# Project_Kondrashova_motor_driver.net
KiCad netlist of a schematic drawn in Altium Designer
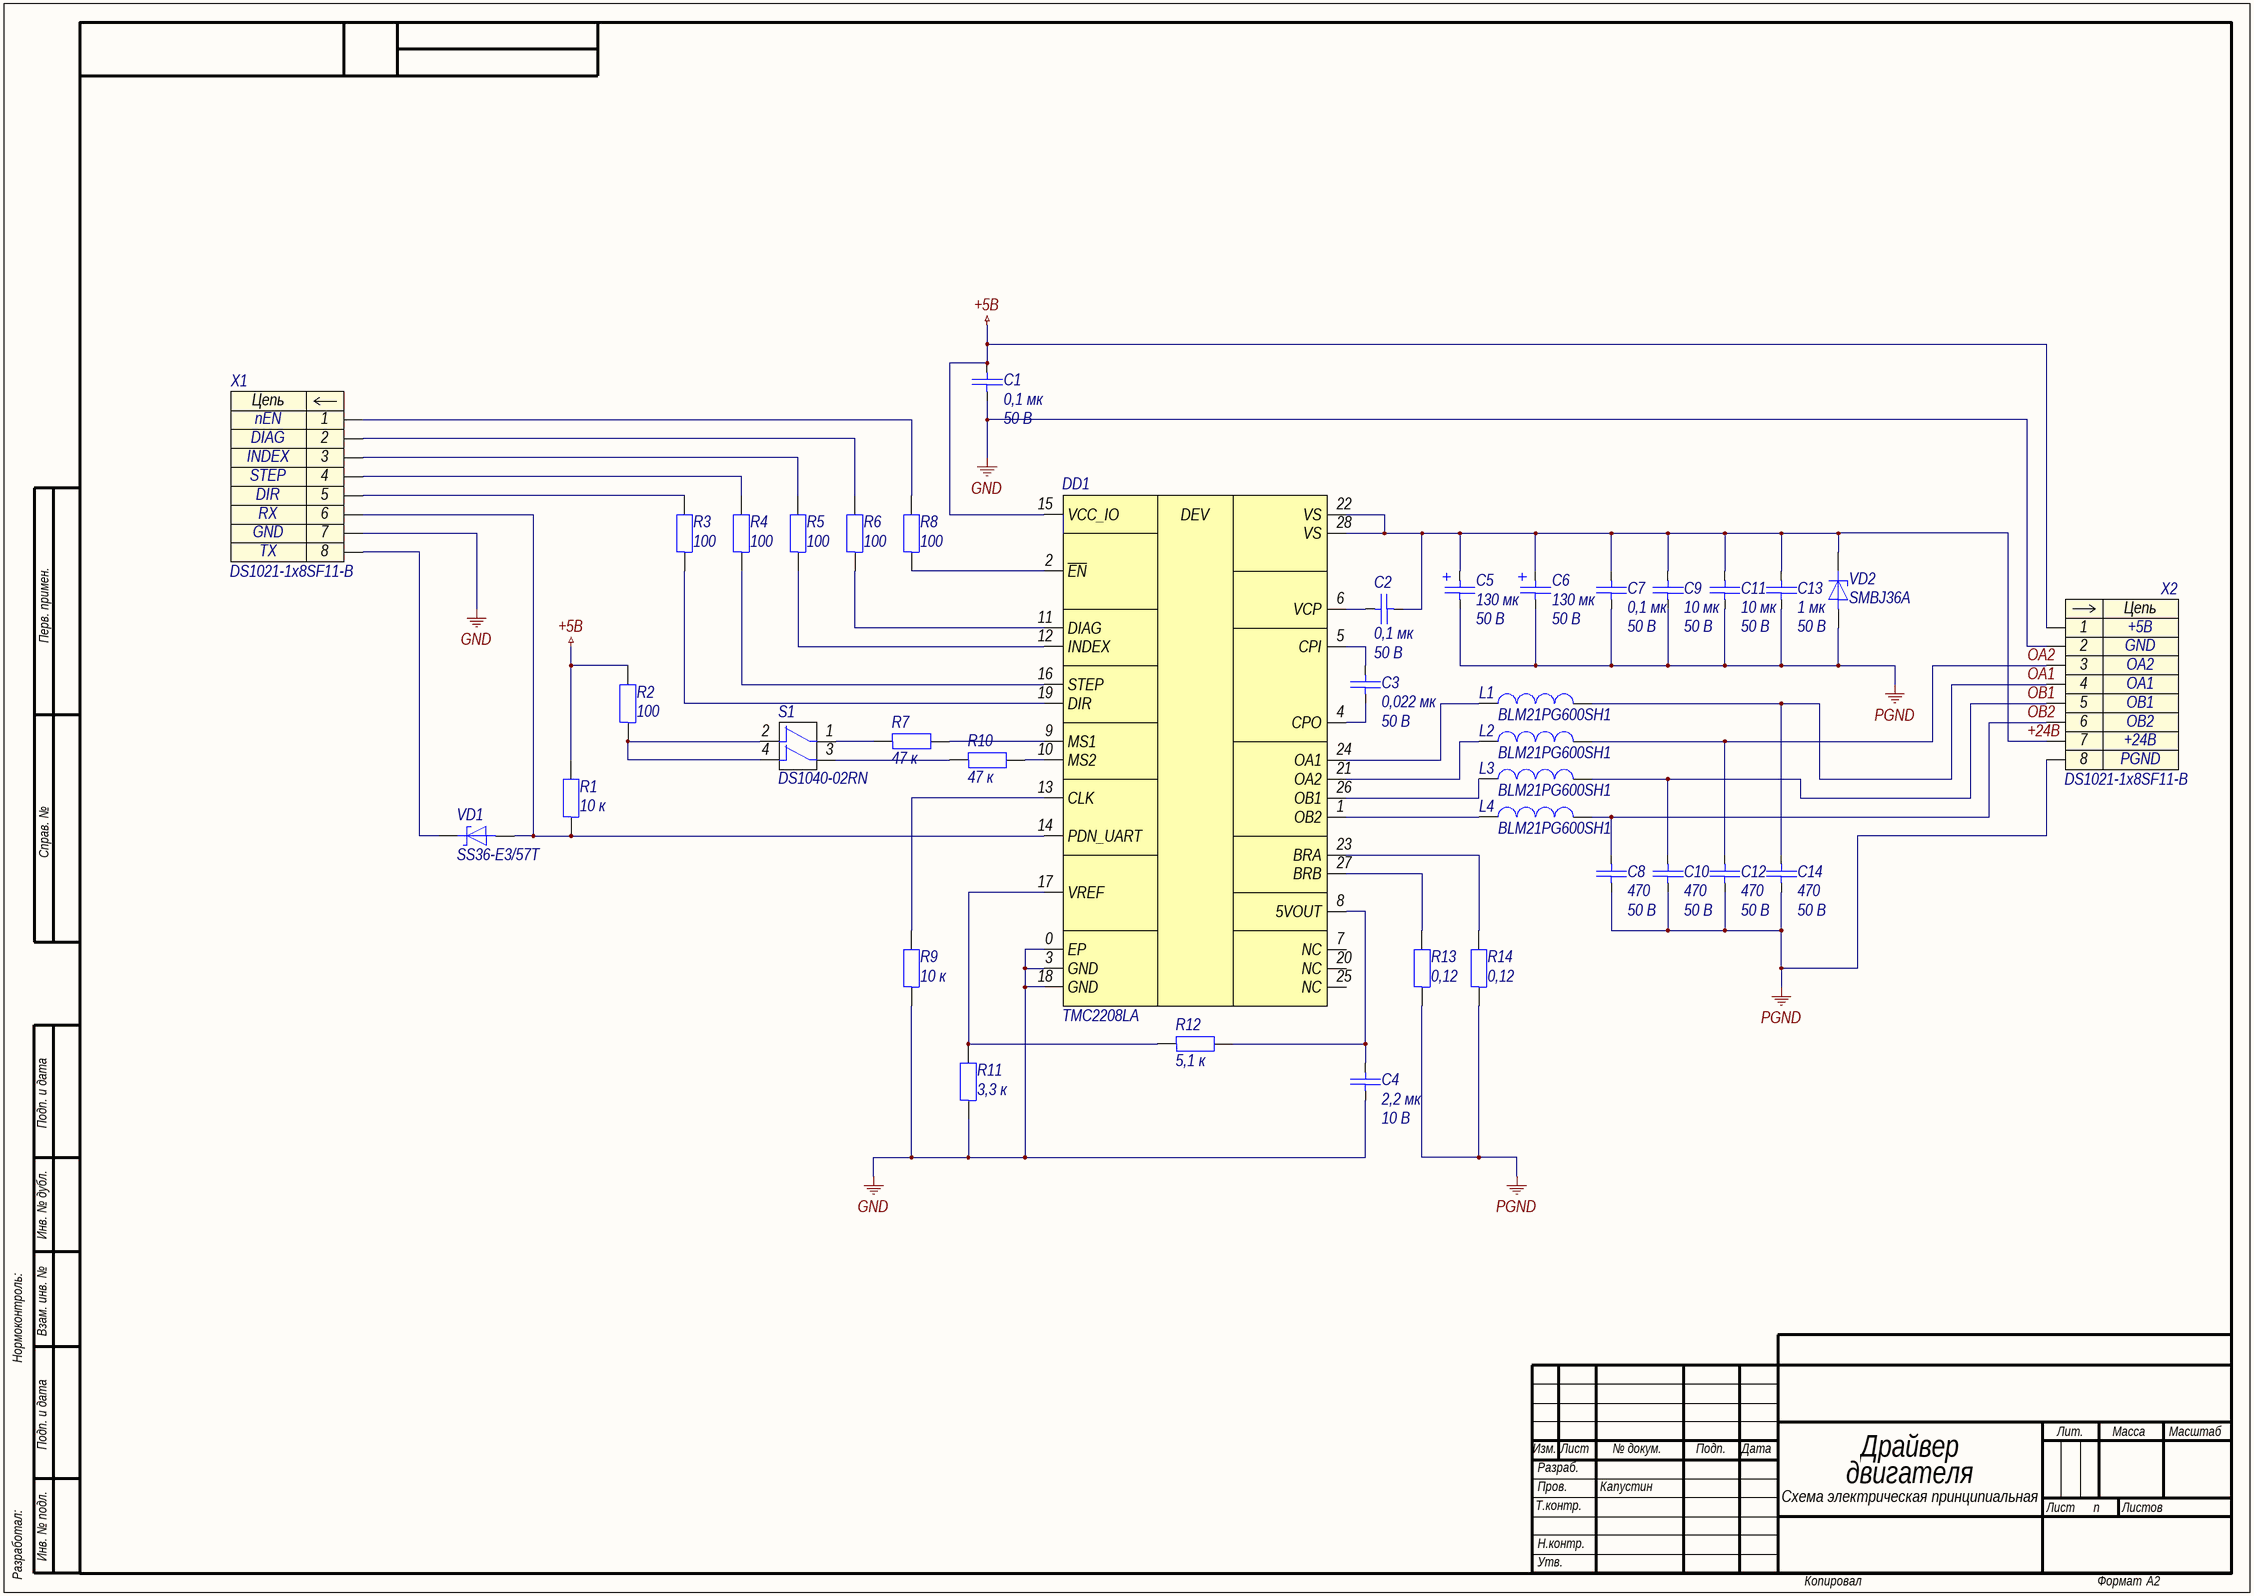
[diagram p0: Project_Kondrashova_motor_driver.SchDoc]

(export (version "E")
  (design (tool "Eeschema 10.0.6"))
  (components
    (comp (ref "C1")
      (value "0,1 мк")
      (footprint "C0603")
      (description "=Описание")
      (fields (field (name "НАПРЯЖЕНИЕ") "50 В"))
      (libsource (lib "Database_Students") (part "CAPACITOR-NONPOLAR"))
    )
    (comp (ref "C2")
      (value "0,1 мк")
      (footprint "C0603")
      (description "=Описание")
      (fields (field (name "НАПРЯЖЕНИЕ") "50 В"))
      (libsource (lib "Database_Students") (part "CAPACITOR-NONPOLAR"))
    )
    (comp (ref "C3")
      (value "0,022 мк")
      (footprint "C0603")
      (description "=Описание")
      (fields (field (name "НАПРЯЖЕНИЕ") "50 В"))
      (libsource (lib "Database_Students") (part "CAPACITOR-NONPOLAR"))
    )
    (comp (ref "C4")
      (value "2,2 мк")
      (footprint "C0603")
      (description "=Описание")
      (fields (field (name "НАПРЯЖЕНИЕ") "10 В"))
      (libsource (lib "Database_Students") (part "CAPACITOR-NONPOLAR"))
    )
    (comp (ref "C5")
      (value "130 мк")
      (footprint "C7343-43")
      (description "=Описание")
      (fields (field (name "НАПРЯЖЕНИЕ") "50 В"))
      (libsource (lib "Database_Students") (part "CAPACITOR-POLAR"))
    )
    (comp (ref "C6")
      (value "130 мк")
      (footprint "C7343-43")
      (description "=Описание")
      (fields (field (name "НАПРЯЖЕНИЕ") "50 В"))
      (libsource (lib "Database_Students") (part "CAPACITOR-POLAR"))
    )
    (comp (ref "C7")
      (value "0,1 мк")
      (footprint "C0603")
      (description "=Описание")
      (fields (field (name "НАПРЯЖЕНИЕ") "50 В"))
      (libsource (lib "Database_Students") (part "CAPACITOR-NONPOLAR"))
    )
    (comp (ref "C8")
      (value "470")
      (footprint "C0603")
      (description "=Описание")
      (fields (field (name "НАПРЯЖЕНИЕ") "50 В"))
      (libsource (lib "Database_Students") (part "CAPACITOR-NONPOLAR"))
    )
    (comp (ref "C9")
      (value "10 мк")
      (footprint "C2220")
      (description "=Описание")
      (fields (field (name "НАПРЯЖЕНИЕ") "50 В"))
      (libsource (lib "Database_Students") (part "CAPACITOR-NONPOLAR"))
    )
    (comp (ref "C10")
      (value "470")
      (footprint "C0603")
      (description "=Описание")
      (fields (field (name "НАПРЯЖЕНИЕ") "50 В"))
      (libsource (lib "Database_Students") (part "CAPACITOR-NONPOLAR"))
    )
    (comp (ref "C11")
      (value "10 мк")
      (footprint "C2220")
      (description "=Описание")
      (fields (field (name "НАПРЯЖЕНИЕ") "50 В"))
      (libsource (lib "Database_Students") (part "CAPACITOR-NONPOLAR"))
    )
    (comp (ref "C12")
      (value "470")
      (footprint "C0603")
      (description "=Описание")
      (fields (field (name "НАПРЯЖЕНИЕ") "50 В"))
      (libsource (lib "Database_Students") (part "CAPACITOR-NONPOLAR"))
    )
    (comp (ref "C13")
      (value "1 мк")
      (footprint "C1210")
      (description "=Описание")
      (fields (field (name "НАПРЯЖЕНИЕ") "50 В"))
      (libsource (lib "Database_Students") (part "CAPACITOR-NONPOLAR"))
    )
    (comp (ref "C14")
      (value "470")
      (footprint "C0603")
      (description "=Описание")
      (fields (field (name "НАПРЯЖЕНИЕ") "50 В"))
      (libsource (lib "Database_Students") (part "CAPACITOR-NONPOLAR"))
    )
    (comp (ref "DD1")
      (value "TMC2208LA")
      (footprint "QFN-28-P50-500X500X90-L55X25-T310X310")
      (description "=Описание")
      (libsource (lib "Database_Students") (part "TMC2208-LA"))
    )
    (comp (ref "L1")
      (value "BLM21PG600SH1")
      (footprint "MI-2-0805")
      (description "=Описание")
      (libsource (lib "Database_Students") (part "FERRITE-BEAD"))
    )
    (comp (ref "L2")
      (value "BLM21PG600SH1")
      (footprint "MI-2-0805")
      (description "=Описание")
      (libsource (lib "Database_Students") (part "FERRITE-BEAD"))
    )
    (comp (ref "L3")
      (value "BLM21PG600SH1")
      (footprint "MI-2-0805")
      (description "=Описание")
      (libsource (lib "Database_Students") (part "FERRITE-BEAD"))
    )
    (comp (ref "L4")
      (value "BLM21PG600SH1")
      (footprint "MI-2-0805")
      (description "=Описание")
      (libsource (lib "Database_Students") (part "FERRITE-BEAD"))
    )
    (comp (ref "R1")
      (value "10 к")
      (footprint "R0603")
      (description "=Описание")
      (libsource (lib "Database_Students") (part "RESISTOR-COMMON"))
    )
    (comp (ref "R2")
      (value "100")
      (footprint "R0603")
      (description "=Описание")
      (libsource (lib "Database_Students") (part "RESISTOR-COMMON"))
    )
    (comp (ref "R3")
      (value "100")
      (footprint "R0603")
      (description "=Описание")
      (libsource (lib "Database_Students") (part "RESISTOR-COMMON"))
    )
    (comp (ref "R4")
      (value "100")
      (footprint "R0603")
      (description "=Описание")
      (libsource (lib "Database_Students") (part "RESISTOR-COMMON"))
    )
    (comp (ref "R5")
      (value "100")
      (footprint "R0603")
      (description "=Описание")
      (libsource (lib "Database_Students") (part "RESISTOR-COMMON"))
    )
    (comp (ref "R6")
      (value "100")
      (footprint "R0603")
      (description "=Описание")
      (libsource (lib "Database_Students") (part "RESISTOR-COMMON"))
    )
    (comp (ref "R7")
      (value "47 к")
      (footprint "R0603")
      (description "=Описание")
      (libsource (lib "Database_Students") (part "RESISTOR-COMMON"))
    )
    (comp (ref "R8")
      (value "100")
      (footprint "R0603")
      (description "=Описание")
      (libsource (lib "Database_Students") (part "RESISTOR-COMMON"))
    )
    (comp (ref "R9")
      (value "10 к")
      (footprint "R0603")
      (description "=Описание")
      (libsource (lib "Database_Students") (part "RESISTOR-COMMON"))
    )
    (comp (ref "R10")
      (value "47 к")
      (footprint "R0603")
      (description "=Описание")
      (libsource (lib "Database_Students") (part "RESISTOR-COMMON"))
    )
    (comp (ref "R11")
      (value "3,3 к")
      (footprint "R0603")
      (description "=Описание")
      (libsource (lib "Database_Students") (part "RESISTOR-COMMON"))
    )
    (comp (ref "R12")
      (value "5,1 к")
      (footprint "R0603")
      (description "=Описание")
      (libsource (lib "Database_Students") (part "RESISTOR-COMMON"))
    )
    (comp (ref "R13")
      (value "0,12")
      (footprint "R0603")
      (description "=Описание")
      (libsource (lib "Database_Students") (part "RESISTOR-COMMON"))
    )
    (comp (ref "R14")
      (value "0,12")
      (footprint "R0603")
      (description "=Описание")
      (libsource (lib "Database_Students") (part "RESISTOR-COMMON"))
    )
    (comp (ref "S1")
      (value "DS1040-02RN")
      (footprint "DS1040-02RN")
      (description "=Описание")
      (libsource (lib "Database_Students") (part "SWITCH-4C"))
    )
    (comp (ref "VD1")
      (value "SS36-E3/57T")
      (footprint "DO-214AB-790X590X262")
      (description "=Описание")
      (libsource (lib "Database_Students") (part "DIODE-SCHOTTKY"))
    )
    (comp (ref "VD2")
      (value "SMBJ36A")
      (footprint "SMBJ36A")
      (description "=Описание")
      (libsource (lib "Database_Students") (part "DIODE-ZENER"))
    )
    (comp (ref "X1")
      (value "DS1021-1x8SF11-B")
      (footprint "DS1021-1X8SF11-B")
      (description "=Описание")
      (libsource (lib "Database_Students") (part "HEADER-8-PLG"))
    )
    (comp (ref "X2")
      (value "DS1021-1x8SF11-B")
      (footprint "DS1021-1X8SF11-B")
      (description "=Описание")
      (libsource (lib "") (part "HEADER-8-PLG_1"))
    )
  )
  (nets
    (net (code "1") (name "+5В") (class "Default")
      (node (ref "C1") (pin "1") (pinfunction "1_1") (pintype "passive"))
      (node (ref "DD1") (pin "15") (pinfunction "VCC_IO_15") (pintype "passive"))
      (node (ref "R1") (pin "2") (pinfunction "2_2") (pintype "passive"))
      (node (ref "R2") (pin "2") (pinfunction "2_2") (pintype "passive"))
      (node (ref "X2") (pin "1") (pinfunction "1_1") (pintype "passive"))
    )
    (net (code "2") (name "/+24В") (class "Default")
      (node (ref "C11") (pin "1") (pinfunction "1_1") (pintype "passive"))
      (node (ref "C13") (pin "1") (pinfunction "1_1") (pintype "passive"))
      (node (ref "C2") (pin "2") (pinfunction "2_2") (pintype "passive"))
      (node (ref "C5") (pin "1") (pinfunction "1_1") (pintype "passive"))
      (node (ref "C6") (pin "1") (pinfunction "1_1") (pintype "passive"))
      (node (ref "C7") (pin "1") (pinfunction "1_1") (pintype "passive"))
      (node (ref "C9") (pin "1") (pinfunction "1_1") (pintype "passive"))
      (node (ref "DD1") (pin "22") (pinfunction "VS_22") (pintype "passive"))
      (node (ref "DD1") (pin "28") (pinfunction "VS_28") (pintype "passive"))
      (node (ref "VD2") (pin "1") (pinfunction "1_1") (pintype "passive"))
      (node (ref "X2") (pin "7") (pinfunction "7_7") (pintype "passive"))
    )
    (net (code "3") (name "/OA1") (class "Default")
      (node (ref "C14") (pin "1") (pinfunction "1_1") (pintype "passive"))
      (node (ref "L1") (pin "2") (pinfunction "2_2") (pintype "passive"))
      (node (ref "X2") (pin "4") (pinfunction "4_4") (pintype "passive"))
    )
    (net (code "4") (name "/OA2") (class "Default")
      (node (ref "C12") (pin "1") (pinfunction "1_1") (pintype "passive"))
      (node (ref "L2") (pin "2") (pinfunction "2_2") (pintype "passive"))
      (node (ref "X2") (pin "3") (pinfunction "3_3") (pintype "passive"))
    )
    (net (code "5") (name "/OB1") (class "Default")
      (node (ref "C10") (pin "1") (pinfunction "1_1") (pintype "passive"))
      (node (ref "L3") (pin "2") (pinfunction "2_2") (pintype "passive"))
      (node (ref "X2") (pin "5") (pinfunction "5_5") (pintype "passive"))
    )
    (net (code "6") (name "/OB2") (class "Default")
      (node (ref "C8") (pin "1") (pinfunction "1_1") (pintype "passive"))
      (node (ref "L4") (pin "2") (pinfunction "2_2") (pintype "passive"))
      (node (ref "X2") (pin "6") (pinfunction "6_6") (pintype "passive"))
    )
    (net (code "7") (name "GND") (class "Default")
      (node (ref "C1") (pin "2") (pinfunction "2_2") (pintype "passive"))
      (node (ref "C4") (pin "2") (pinfunction "2_2") (pintype "passive"))
      (node (ref "DD1") (pin "0") (pinfunction "EP_0") (pintype "passive"))
      (node (ref "DD1") (pin "18") (pinfunction "GND_18") (pintype "passive"))
      (node (ref "DD1") (pin "3") (pinfunction "GND_3") (pintype "passive"))
      (node (ref "R11") (pin "1") (pinfunction "1_1") (pintype "passive"))
      (node (ref "R9") (pin "1") (pinfunction "1_1") (pintype "passive"))
      (node (ref "X1") (pin "7") (pinfunction "7_7") (pintype "passive"))
      (node (ref "X2") (pin "2") (pinfunction "2_2") (pintype "passive"))
    )
    (net (code "8") (name "Net-(DD1-5VOUT)") (class "Default")
      (node (ref "C4") (pin "1") (pinfunction "1_1") (pintype "passive"))
      (node (ref "DD1") (pin "8") (pinfunction "5VOUT_8") (pintype "passive"))
      (node (ref "R12") (pin "2") (pinfunction "2_2") (pintype "passive"))
    )
    (net (code "9") (name "Net-(DD1-BRA)") (class "Default")
      (node (ref "DD1") (pin "23") (pinfunction "BRA_23") (pintype "passive"))
      (node (ref "R14") (pin "2") (pinfunction "2_2") (pintype "passive"))
    )
    (net (code "10") (name "Net-(DD1-BRB)") (class "Default")
      (node (ref "DD1") (pin "27") (pinfunction "BRB_27") (pintype "passive"))
      (node (ref "R13") (pin "2") (pinfunction "2_2") (pintype "passive"))
    )
    (net (code "11") (name "Net-(DD1-CLK)") (class "Default")
      (node (ref "DD1") (pin "13") (pinfunction "CLK_13") (pintype "passive"))
      (node (ref "R9") (pin "2") (pinfunction "2_2") (pintype "passive"))
    )
    (net (code "12") (name "Net-(DD1-CPI)") (class "Default")
      (node (ref "C3") (pin "1") (pinfunction "1_1") (pintype "passive"))
      (node (ref "DD1") (pin "5") (pinfunction "CPI_5") (pintype "passive"))
    )
    (net (code "13") (name "Net-(DD1-CPO)") (class "Default")
      (node (ref "C3") (pin "2") (pinfunction "2_2") (pintype "passive"))
      (node (ref "DD1") (pin "4") (pinfunction "CPO_4") (pintype "passive"))
    )
    (net (code "14") (name "Net-(DD1-DIAG)") (class "Default")
      (node (ref "DD1") (pin "11") (pinfunction "DIAG_11") (pintype "passive"))
      (node (ref "R6") (pin "1") (pinfunction "1_1") (pintype "passive"))
    )
    (net (code "15") (name "Net-(DD1-DIR)") (class "Default")
      (node (ref "DD1") (pin "19") (pinfunction "DIR_19") (pintype "passive"))
      (node (ref "R3") (pin "1") (pinfunction "1_1") (pintype "passive"))
    )
    (net (code "16") (name "Net-(DD1-INDEX)") (class "Default")
      (node (ref "DD1") (pin "12") (pinfunction "INDEX_12") (pintype "passive"))
      (node (ref "R5") (pin "1") (pinfunction "1_1") (pintype "passive"))
    )
    (net (code "17") (name "Net-(DD1-MS1)") (class "Default")
      (node (ref "DD1") (pin "9") (pinfunction "MS1_9") (pintype "passive"))
      (node (ref "R7") (pin "2") (pinfunction "2_2") (pintype "passive"))
    )
    (net (code "18") (name "Net-(DD1-MS2)") (class "Default")
      (node (ref "DD1") (pin "10") (pinfunction "MS2_10") (pintype "passive"))
      (node (ref "R10") (pin "2") (pinfunction "2_2") (pintype "passive"))
    )
    (net (code "19") (name "Net-(DD1-OA1)") (class "Default")
      (node (ref "DD1") (pin "24") (pinfunction "OA1_24") (pintype "passive"))
      (node (ref "L1") (pin "1") (pinfunction "1_1") (pintype "passive"))
    )
    (net (code "20") (name "Net-(DD1-OA2)") (class "Default")
      (node (ref "DD1") (pin "21") (pinfunction "OA2_21") (pintype "passive"))
      (node (ref "L2") (pin "1") (pinfunction "1_1") (pintype "passive"))
    )
    (net (code "21") (name "Net-(DD1-OB1)") (class "Default")
      (node (ref "DD1") (pin "26") (pinfunction "OB1_26") (pintype "passive"))
      (node (ref "L3") (pin "1") (pinfunction "1_1") (pintype "passive"))
    )
    (net (code "22") (name "Net-(DD1-OB2)") (class "Default")
      (node (ref "DD1") (pin "1") (pinfunction "OB2_1") (pintype "passive"))
      (node (ref "L4") (pin "1") (pinfunction "1_1") (pintype "passive"))
    )
    (net (code "23") (name "Net-(DD1-PDN_UART)") (class "Default")
      (node (ref "DD1") (pin "14") (pinfunction "PDN_UART_14") (pintype "passive"))
      (node (ref "R1") (pin "1") (pinfunction "1_1") (pintype "passive"))
      (node (ref "VD1") (pin "2") (pinfunction "2_2") (pintype "passive"))
      (node (ref "X1") (pin "6") (pinfunction "6_6") (pintype "passive"))
    )
    (net (code "24") (name "Net-(DD1-STEP)") (class "Default")
      (node (ref "DD1") (pin "16") (pinfunction "STEP_16") (pintype "passive"))
      (node (ref "R4") (pin "1") (pinfunction "1_1") (pintype "passive"))
    )
    (net (code "25") (name "Net-(DD1-VCP)") (class "Default")
      (node (ref "C2") (pin "1") (pinfunction "1_1") (pintype "passive"))
      (node (ref "DD1") (pin "6") (pinfunction "VCP_6") (pintype "passive"))
    )
    (net (code "26") (name "Net-(DD1-VREF)") (class "Default")
      (node (ref "DD1") (pin "17") (pinfunction "VREF_17") (pintype "passive"))
      (node (ref "R11") (pin "2") (pinfunction "2_2") (pintype "passive"))
      (node (ref "R12") (pin "1") (pinfunction "1_1") (pintype "passive"))
    )
    (net (code "27") (name "Net-(DD1-~{EN})") (class "Default")
      (node (ref "DD1") (pin "2") (pinfunction "~{EN}_2") (pintype "passive"))
      (node (ref "R8") (pin "1") (pinfunction "1_1") (pintype "passive"))
    )
    (net (code "28") (name "Net-(R2-Pad1)") (class "Default")
      (node (ref "R2") (pin "1") (pinfunction "1_1") (pintype "passive"))
      (node (ref "S1") (pin "2") (pinfunction "2_2") (pintype "passive"))
      (node (ref "S1") (pin "4") (pinfunction "4_4") (pintype "passive"))
    )
    (net (code "29") (name "Net-(R3-Pad2)") (class "Default")
      (node (ref "R3") (pin "2") (pinfunction "2_2") (pintype "passive"))
      (node (ref "X1") (pin "5") (pinfunction "5_5") (pintype "passive"))
    )
    (net (code "30") (name "Net-(R4-Pad2)") (class "Default")
      (node (ref "R4") (pin "2") (pinfunction "2_2") (pintype "passive"))
      (node (ref "X1") (pin "4") (pinfunction "4_4") (pintype "passive"))
    )
    (net (code "31") (name "Net-(R5-Pad2)") (class "Default")
      (node (ref "R5") (pin "2") (pinfunction "2_2") (pintype "passive"))
      (node (ref "X1") (pin "3") (pinfunction "3_3") (pintype "passive"))
    )
    (net (code "32") (name "Net-(R6-Pad2)") (class "Default")
      (node (ref "R6") (pin "2") (pinfunction "2_2") (pintype "passive"))
      (node (ref "X1") (pin "2") (pinfunction "2_2") (pintype "passive"))
    )
    (net (code "33") (name "Net-(R7-Pad1)") (class "Default")
      (node (ref "R7") (pin "1") (pinfunction "1_1") (pintype "passive"))
      (node (ref "S1") (pin "1") (pinfunction "1_1") (pintype "passive"))
    )
    (net (code "34") (name "Net-(R8-Pad2)") (class "Default")
      (node (ref "R8") (pin "2") (pinfunction "2_2") (pintype "passive"))
      (node (ref "X1") (pin "1") (pinfunction "1_1") (pintype "passive"))
    )
    (net (code "35") (name "Net-(R10-Pad1)") (class "Default")
      (node (ref "R10") (pin "1") (pinfunction "1_1") (pintype "passive"))
      (node (ref "S1") (pin "3") (pinfunction "3_3") (pintype "passive"))
    )
    (net (code "36") (name "Net-(VD1-Pad1)") (class "Default")
      (node (ref "VD1") (pin "1") (pinfunction "1_1") (pintype "passive"))
      (node (ref "X1") (pin "8") (pinfunction "8_8") (pintype "passive"))
    )
    (net (code "37") (name "PGND") (class "Default")
      (node (ref "C10") (pin "2") (pinfunction "2_2") (pintype "passive"))
      (node (ref "C11") (pin "2") (pinfunction "2_2") (pintype "passive"))
      (node (ref "C12") (pin "2") (pinfunction "2_2") (pintype "passive"))
      (node (ref "C13") (pin "2") (pinfunction "2_2") (pintype "passive"))
      (node (ref "C14") (pin "2") (pinfunction "2_2") (pintype "passive"))
      (node (ref "C5") (pin "2") (pinfunction "2_2") (pintype "passive"))
      (node (ref "C6") (pin "2") (pinfunction "2_2") (pintype "passive"))
      (node (ref "C7") (pin "2") (pinfunction "2_2") (pintype "passive"))
      (node (ref "C8") (pin "2") (pinfunction "2_2") (pintype "passive"))
      (node (ref "C9") (pin "2") (pinfunction "2_2") (pintype "passive"))
      (node (ref "R13") (pin "1") (pinfunction "1_1") (pintype "passive"))
      (node (ref "R14") (pin "1") (pinfunction "1_1") (pintype "passive"))
      (node (ref "VD2") (pin "2") (pinfunction "2_2") (pintype "passive"))
      (node (ref "X2") (pin "8") (pinfunction "8_8") (pintype "passive"))
    )
    (net (code "38") (name "unconnected-(DD1-NC-Pad7)") (class "Default")
      (node (ref "DD1") (pin "7") (pinfunction "NC_7") (pintype "passive"))
    )
    (net (code "39") (name "unconnected-(DD1-NC-Pad20)") (class "Default")
      (node (ref "DD1") (pin "20") (pinfunction "NC_20") (pintype "passive"))
    )
    (net (code "40") (name "unconnected-(DD1-NC-Pad25)") (class "Default")
      (node (ref "DD1") (pin "25") (pinfunction "NC_25") (pintype "passive"))
    )
  )
)
